# sch_alim.net
KiCad netlist of a schematic drawn in Altium Designer
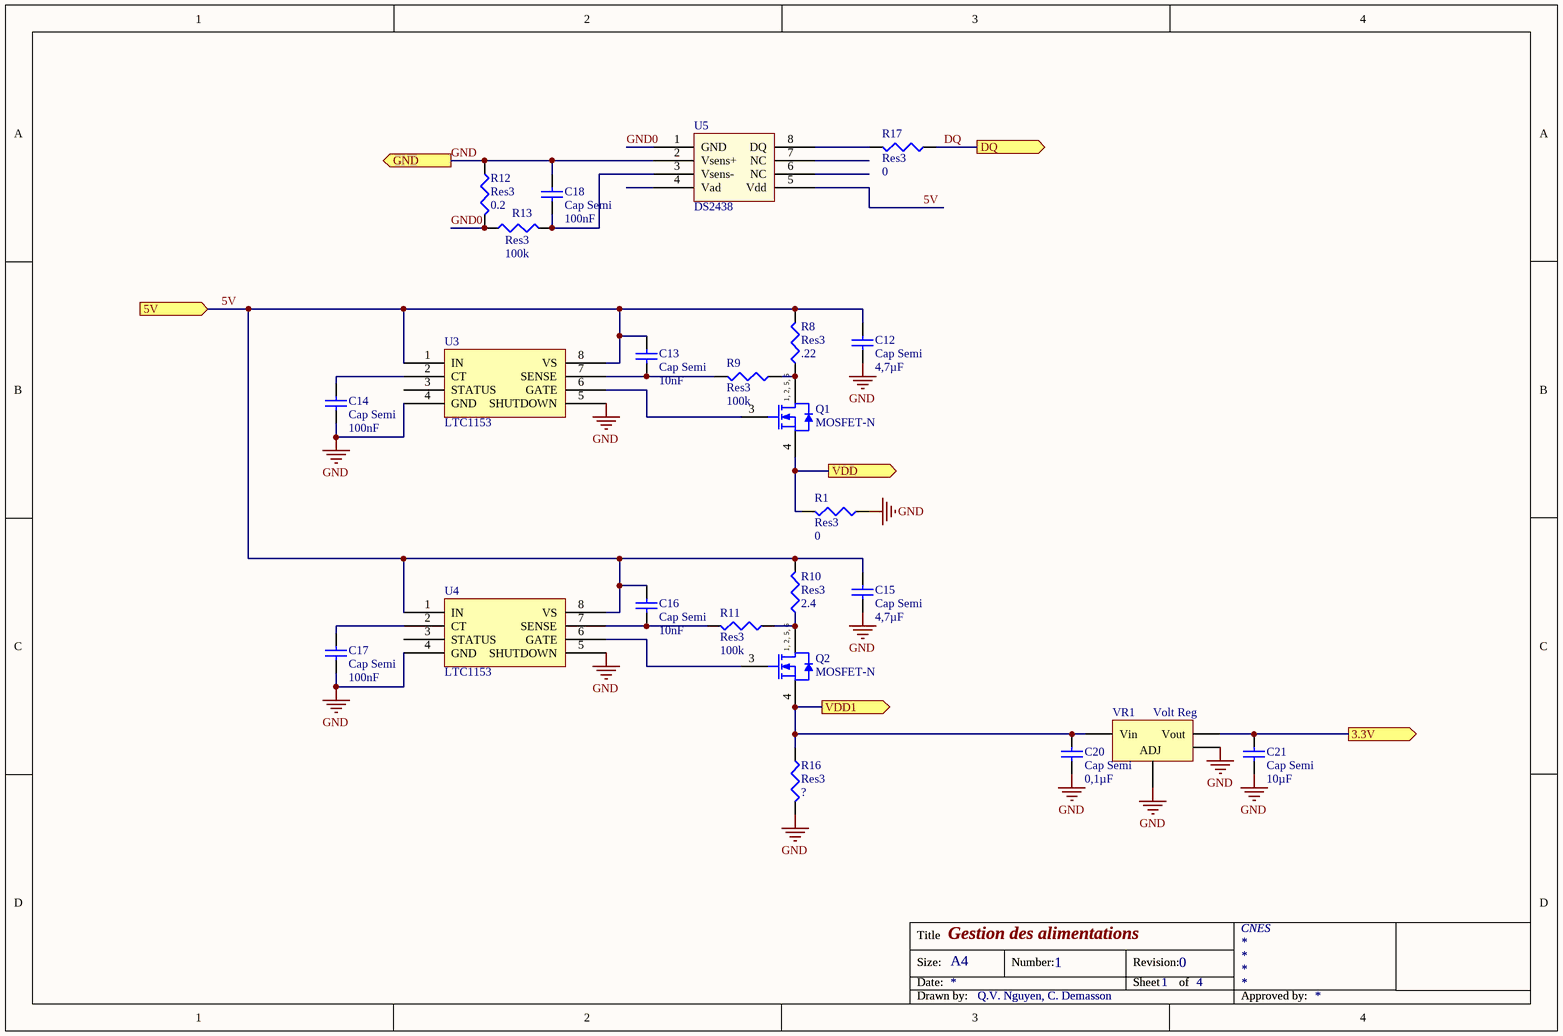
[diagram p0: sch_alim.SchDoc]

(export (version "E")
  (design (tool "Eeschema 10.0.6"))
  (components
    (comp (ref "C12")
      (value "Cap Semi")
      (footprint "C1206")
      (description "Capacitor (Semiconductor SIM Model)")
      (fields (field (name "ALTIUM_VALUE") "4,7µF") (field (name "PUBLISHER") "Altium Limited"))
      (libsource (lib "Miscellaneous Devices") (part "Cap Semi"))
    )
    (comp (ref "C13")
      (value "Cap Semi")
      (footprint "C1206")
      (description "Capacitor (Semiconductor SIM Model)")
      (fields (field (name "ALTIUM_VALUE") "10nF") (field (name "PUBLISHER") "Altium Limited"))
      (libsource (lib "Miscellaneous Devices") (part "Cap Semi"))
    )
    (comp (ref "C14")
      (value "Cap Semi")
      (footprint "C1206")
      (description "Capacitor (Semiconductor SIM Model)")
      (fields (field (name "ALTIUM_VALUE") "100nF") (field (name "PUBLISHER") "Altium Limited"))
      (libsource (lib "Miscellaneous Devices") (part "Cap Semi"))
    )
    (comp (ref "C15")
      (value "Cap Semi")
      (footprint "C1206")
      (description "Capacitor (Semiconductor SIM Model)")
      (fields (field (name "ALTIUM_VALUE") "4,7µF") (field (name "PUBLISHER") "Altium Limited"))
      (libsource (lib "Miscellaneous Devices") (part "Cap Semi"))
    )
    (comp (ref "C16")
      (value "Cap Semi")
      (footprint "C1206")
      (description "Capacitor (Semiconductor SIM Model)")
      (fields (field (name "ALTIUM_VALUE") "10nF") (field (name "PUBLISHER") "Altium Limited"))
      (libsource (lib "Miscellaneous Devices") (part "Cap Semi"))
    )
    (comp (ref "C17")
      (value "Cap Semi")
      (footprint "C1206")
      (description "Capacitor (Semiconductor SIM Model)")
      (fields (field (name "ALTIUM_VALUE") "100nF") (field (name "PUBLISHER") "Altium Limited"))
      (libsource (lib "Miscellaneous Devices") (part "Cap Semi"))
    )
    (comp (ref "C18")
      (value "Cap Semi")
      (footprint "C1206")
      (description "Capacitor (Semiconductor SIM Model)")
      (fields (field (name "ALTIUM_VALUE") "100nF") (field (name "PUBLISHER") "Altium Limited"))
      (libsource (lib "Miscellaneous Devices") (part "Cap Semi"))
    )
    (comp (ref "C20")
      (value "Cap Semi")
      (footprint "C1206")
      (description "Capacitor (Semiconductor SIM Model)")
      (fields (field (name "ALTIUM_VALUE") "0,1µF") (field (name "PUBLISHER") "Altium Limited"))
      (libsource (lib "Miscellaneous Devices") (part "Cap Semi"))
    )
    (comp (ref "C21")
      (value "Cap Semi")
      (footprint "C1206")
      (description "Capacitor (Semiconductor SIM Model)")
      (fields (field (name "ALTIUM_VALUE") "10µF") (field (name "PUBLISHER") "Altium Limited"))
      (libsource (lib "Miscellaneous Devices") (part "Cap Semi"))
    )
    (comp (ref "Q1")
      (value "MOSFET-N")
      (footprint "ONSC-SC70-6-419B-02_V")
      (description "Trench Power MOSFET, 20 V, 4 A, Single N-Channel, 6-Pin SC70, Pb-Free, Tape and Reel")
      (fields (field (name "PARTNUMBER") "NTJS3157NT2G") (field (name "MANUFACTURER") "On Semiconductor"))
      (libsource (lib "Altium Content Vault") (part "ONSC-NMOS-6_C"))
    )
    (comp (ref "Q2")
      (value "MOSFET-N")
      (footprint "ONSC-SC70-6-419B-02_V")
      (description "Trench Power MOSFET, 20 V, 4 A, Single N-Channel, 6-Pin SC70, Pb-Free, Tape and Reel")
      (fields (field (name "PARTNUMBER") "NTJS3157NT2G") (field (name "MANUFACTURER") "On Semiconductor"))
      (libsource (lib "Altium Content Vault") (part "ONSC-NMOS-6_C"))
    )
    (comp (ref "R1")
      (value "Res3")
      (footprint "C1206")
      (description "Resistor")
      (fields (field (name "ALTIUM_VALUE") "0") (field (name "PUBLISHER") "Altium Limited"))
      (libsource (lib "Miscellaneous Devices") (part "Res3"))
    )
    (comp (ref "R8")
      (value "Res3")
      (footprint "C1206")
      (description "Resistor")
      (fields (field (name "ALTIUM_VALUE") ".22") (field (name "PUBLISHER") "Altium Limited"))
      (libsource (lib "Miscellaneous Devices") (part "Res3"))
    )
    (comp (ref "R9")
      (value "Res3")
      (footprint "C1206")
      (description "Resistor")
      (fields (field (name "ALTIUM_VALUE") "100k") (field (name "PUBLISHER") "Altium Limited"))
      (libsource (lib "Miscellaneous Devices") (part "Res3"))
    )
    (comp (ref "R10")
      (value "Res3")
      (footprint "C1206")
      (description "Resistor")
      (fields (field (name "ALTIUM_VALUE") "2.4") (field (name "PUBLISHER") "Altium Limited"))
      (libsource (lib "Miscellaneous Devices") (part "Res3"))
    )
    (comp (ref "R11")
      (value "Res3")
      (footprint "C1206")
      (description "Resistor")
      (fields (field (name "ALTIUM_VALUE") "100k") (field (name "PUBLISHER") "Altium Limited"))
      (libsource (lib "Miscellaneous Devices") (part "Res3"))
    )
    (comp (ref "R12")
      (value "Res3")
      (footprint "C1206")
      (description "Resistor")
      (fields (field (name "ALTIUM_VALUE") "0.2") (field (name "PUBLISHER") "Altium Limited"))
      (libsource (lib "Miscellaneous Devices") (part "Res3"))
    )
    (comp (ref "R13")
      (value "Res3")
      (footprint "C1206")
      (description "Resistor")
      (fields (field (name "ALTIUM_VALUE") "100k") (field (name "PUBLISHER") "Altium Limited"))
      (libsource (lib "Miscellaneous Devices") (part "Res3"))
    )
    (comp (ref "R16")
      (value "Res3")
      (footprint "C1206")
      (description "Resistor")
      (fields (field (name "ALTIUM_VALUE") "?") (field (name "PUBLISHER") "Altium Limited"))
      (libsource (lib "Miscellaneous Devices") (part "Res3"))
    )
    (comp (ref "R17")
      (value "Res3")
      (footprint "C1206")
      (description "Resistor")
      (fields (field (name "ALTIUM_VALUE") "0") (field (name "PUBLISHER") "Altium Limited"))
      (libsource (lib "Miscellaneous Devices") (part "Res3"))
    )
    (comp (ref "U3")
      (value "LTC1153")
      (footprint "S8 Package")
      (libsource (lib "SCH_LIB_EPM") (part "LTC1153"))
    )
    (comp (ref "U4")
      (value "LTC1153")
      (footprint "S8 Package")
      (libsource (lib "SCH_LIB_EPM") (part "LTC1153"))
    )
    (comp (ref "U5")
      (value "DS2438")
      (footprint "SO8_N")
      (description "Battery Monitor")
      (libsource (lib "SCH_LIB_EPM") (part "DS2438"))
    )
    (comp (ref "VR1")
      (value "Volt Reg")
      (footprint "Reg_LM317")
      (description "Voltage Regulator")
      (fields (field (name "PUBLISHER") "Altium Limited"))
      (libsource (lib "SCH_LIB_EPM") (part "Volt Reg"))
    )
  )
  (nets
    (net (code "1") (name "/3.3V") (class "Default")
      (node (ref "C21") (pin "1") (pinfunction "1_1") (pintype "passive"))
      (node (ref "VR1") (pin "3") (pinfunction "Vout_3") (pintype "passive"))
    )
    (net (code "2") (name "/5V") (class "Default")
      (node (ref "C12") (pin "1") (pinfunction "1_1") (pintype "passive"))
      (node (ref "C13") (pin "1") (pinfunction "1_1") (pintype "passive"))
      (node (ref "C15") (pin "1") (pinfunction "1_1") (pintype "passive"))
      (node (ref "C16") (pin "1") (pinfunction "1_1") (pintype "passive"))
      (node (ref "R10") (pin "2") (pinfunction "2_2") (pintype "passive"))
      (node (ref "R8") (pin "2") (pinfunction "2_2") (pintype "passive"))
      (node (ref "U3") (pin "1") (pinfunction "IN_1") (pintype "passive"))
      (node (ref "U3") (pin "8") (pinfunction "VS_8") (pintype "passive"))
      (node (ref "U4") (pin "1") (pinfunction "IN_1") (pintype "passive"))
      (node (ref "U4") (pin "8") (pinfunction "VS_8") (pintype "passive"))
      (node (ref "U5") (pin "5") (pinfunction "Vdd_5") (pintype "passive"))
    )
    (net (code "3") (name "/DQ") (class "Default")
      (node (ref "R17") (pin "1") (pinfunction "1_1") (pintype "passive"))
    )
    (net (code "4") (name "/GND0") (class "Default")
      (node (ref "R12") (pin "2") (pinfunction "2_2") (pintype "passive"))
      (node (ref "R13") (pin "1") (pinfunction "1_1") (pintype "passive"))
      (node (ref "U5") (pin "1") (pinfunction "GND_1") (pintype "passive"))
    )
    (net (code "5") (name "/VDD") (class "Default")
      (node (ref "Q1") (pin "4") (pinfunction "S_4") (pintype "passive"))
      (node (ref "R1") (pin "2") (pinfunction "2_2") (pintype "passive"))
    )
    (net (code "6") (name "/VDD1") (class "Default")
      (node (ref "C20") (pin "1") (pinfunction "1_1") (pintype "passive"))
      (node (ref "Q2") (pin "4") (pinfunction "S_4") (pintype "passive"))
      (node (ref "R16") (pin "1") (pinfunction "1_1") (pintype "passive"))
      (node (ref "VR1") (pin "1") (pinfunction "Vin_1") (pintype "passive"))
    )
    (net (code "7") (name "GND") (class "Default")
      (node (ref "C12") (pin "2") (pinfunction "2_2") (pintype "passive"))
      (node (ref "C14") (pin "2") (pinfunction "2_2") (pintype "passive"))
      (node (ref "C15") (pin "2") (pinfunction "2_2") (pintype "passive"))
      (node (ref "C17") (pin "2") (pinfunction "2_2") (pintype "passive"))
      (node (ref "C18") (pin "1") (pinfunction "1_1") (pintype "passive"))
      (node (ref "C20") (pin "2") (pinfunction "2_2") (pintype "passive"))
      (node (ref "C21") (pin "2") (pinfunction "2_2") (pintype "passive"))
      (node (ref "R1") (pin "1") (pinfunction "1_1") (pintype "passive"))
      (node (ref "R12") (pin "1") (pinfunction "1_1") (pintype "passive"))
      (node (ref "R16") (pin "2") (pinfunction "2_2") (pintype "passive"))
      (node (ref "U3") (pin "4") (pinfunction "GND_4") (pintype "passive"))
      (node (ref "U3") (pin "5") (pinfunction "SHUTDOWN_5") (pintype "passive"))
      (node (ref "U4") (pin "4") (pinfunction "GND_4") (pintype "passive"))
      (node (ref "U4") (pin "5") (pinfunction "SHUTDOWN_5") (pintype "passive"))
      (node (ref "U5") (pin "2") (pinfunction "Vsens+_2") (pintype "passive"))
      (node (ref "VR1") (pin "2") (pinfunction "ADJ_2") (pintype "passive"))
      (node (ref "VR1") (pin "4") (pinfunction "Vout_4") (pintype "passive"))
    )
    (net (code "8") (name "Net-(Q1-D-Pad1)") (class "Default")
      (node (ref "Q1") (pin "1") (pinfunction "D_1") (pintype "passive"))
      (node (ref "Q1") (pin "2") (pinfunction "D_2") (pintype "passive"))
      (node (ref "Q1") (pin "5") (pinfunction "D_5") (pintype "passive"))
      (node (ref "Q1") (pin "6") (pinfunction "D_6") (pintype "passive"))
      (node (ref "R8") (pin "1") (pinfunction "1_1") (pintype "passive"))
      (node (ref "R9") (pin "1") (pinfunction "1_1") (pintype "passive"))
    )
    (net (code "9") (name "Net-(Q1-G)") (class "Default")
      (node (ref "Q1") (pin "3") (pinfunction "G_3") (pintype "passive"))
      (node (ref "U3") (pin "6") (pinfunction "GATE_6") (pintype "passive"))
    )
    (net (code "10") (name "Net-(Q2-D-Pad1)") (class "Default")
      (node (ref "Q2") (pin "1") (pinfunction "D_1") (pintype "passive"))
      (node (ref "Q2") (pin "2") (pinfunction "D_2") (pintype "passive"))
      (node (ref "Q2") (pin "5") (pinfunction "D_5") (pintype "passive"))
      (node (ref "Q2") (pin "6") (pinfunction "D_6") (pintype "passive"))
      (node (ref "R10") (pin "1") (pinfunction "1_1") (pintype "passive"))
      (node (ref "R11") (pin "1") (pinfunction "1_1") (pintype "passive"))
    )
    (net (code "11") (name "Net-(Q2-G)") (class "Default")
      (node (ref "Q2") (pin "3") (pinfunction "G_3") (pintype "passive"))
      (node (ref "U4") (pin "6") (pinfunction "GATE_6") (pintype "passive"))
    )
    (net (code "12") (name "Net-(U3-CT)") (class "Default")
      (node (ref "C14") (pin "1") (pinfunction "1_1") (pintype "passive"))
      (node (ref "U3") (pin "2") (pinfunction "CT_2") (pintype "passive"))
    )
    (net (code "13") (name "Net-(U3-SENSE)") (class "Default")
      (node (ref "C13") (pin "2") (pinfunction "2_2") (pintype "passive"))
      (node (ref "R9") (pin "2") (pinfunction "2_2") (pintype "passive"))
      (node (ref "U3") (pin "7") (pinfunction "SENSE_7") (pintype "passive"))
    )
    (net (code "14") (name "Net-(U4-CT)") (class "Default")
      (node (ref "C17") (pin "1") (pinfunction "1_1") (pintype "passive"))
      (node (ref "U4") (pin "2") (pinfunction "CT_2") (pintype "passive"))
    )
    (net (code "15") (name "Net-(U4-SENSE)") (class "Default")
      (node (ref "C16") (pin "2") (pinfunction "2_2") (pintype "passive"))
      (node (ref "R11") (pin "2") (pinfunction "2_2") (pintype "passive"))
      (node (ref "U4") (pin "7") (pinfunction "SENSE_7") (pintype "passive"))
    )
    (net (code "16") (name "Net-(U5-DQ)") (class "Default")
      (node (ref "R17") (pin "2") (pinfunction "2_2") (pintype "passive"))
      (node (ref "U5") (pin "8") (pinfunction "DQ_8") (pintype "passive"))
    )
    (net (code "17") (name "Net-(U5-Vsens-)") (class "Default")
      (node (ref "C18") (pin "2") (pinfunction "2_2") (pintype "passive"))
      (node (ref "R13") (pin "2") (pinfunction "2_2") (pintype "passive"))
      (node (ref "U5") (pin "3") (pinfunction "Vsens-_3") (pintype "passive"))
    )
    (net (code "18") (name "unconnected-(U3-STATUS-Pad3)") (class "Default")
      (node (ref "U3") (pin "3") (pinfunction "STATUS_3") (pintype "passive"))
    )
    (net (code "19") (name "unconnected-(U4-STATUS-Pad3)") (class "Default")
      (node (ref "U4") (pin "3") (pinfunction "STATUS_3") (pintype "passive"))
    )
    (net (code "20") (name "unconnected-(U5-NC-Pad6)") (class "Default")
      (node (ref "U5") (pin "6") (pinfunction "NC_6") (pintype "passive"))
    )
    (net (code "21") (name "unconnected-(U5-NC-Pad7)") (class "Default")
      (node (ref "U5") (pin "7") (pinfunction "NC_7") (pintype "passive"))
    )
    (net (code "22") (name "unconnected-(U5-Vad-Pad4)") (class "Default")
      (node (ref "U5") (pin "4") (pinfunction "Vad_4") (pintype "passive"))
    )
  )
)
